# cm_filter_ch1_a.net
KiCad netlist of a schematic drawn in Altium Designer
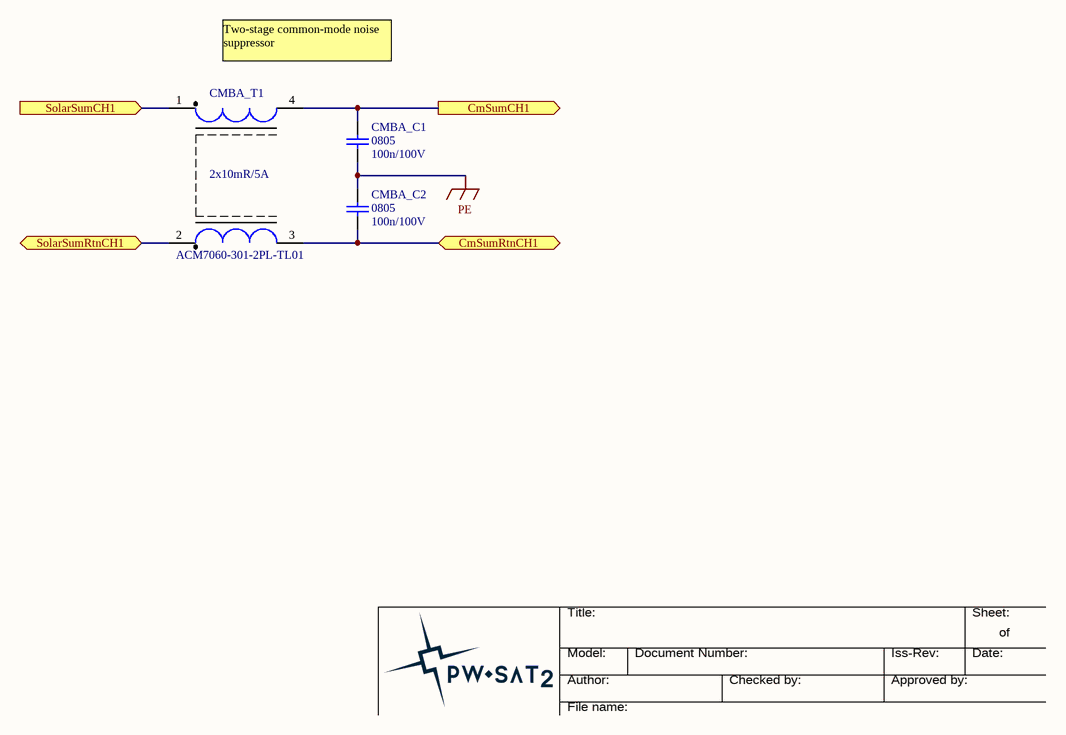
[diagram p0: cm_filter_ch1_a.SchDoc]

(export (version "E")
  (design (tool "Eeschema 10.0.6"))
  (components
    (comp (ref "CMBA_C1")
      (value "100n/100V")
      (footprint "SMD_Capacitor_0805")
      (description "Ceramic Cap Kemet COTS 100n/100V X7R 0805")
      (fields
        (field (name "MANUFACTURERPARTNUMBER") "C0805T104K1RCLTU")
        (field (name "MANUFACTURER") "Kemet")
        (field (name "PACKAGE") "0805")
      )
      (libsource (lib "capacitors") (part "Cer_C0805T104K1RCLTU"))
    )
    (comp (ref "CMBA_C2")
      (value "100n/100V")
      (footprint "SMD_Capacitor_0805")
      (description "Ceramic Cap Kemet COTS 100n/100V X7R 0805")
      (fields
        (field (name "MANUFACTURERPARTNUMBER") "C0805T104K1RCLTU")
        (field (name "MANUFACTURER") "Kemet")
        (field (name "PACKAGE") "0805")
      )
      (libsource (lib "capacitors") (part "Cer_C0805T104K1RCLTU"))
    )
    (comp (ref "CMBA_T1")
      (value "2x10mR/5A")
      (footprint "TDK_ACM7060")
      (description "TDK ACM7060-301 Common Mode Choke")
      (fields
        (field (name "MANUFACTURER") "TDK")
        (field (name "MANUFACTURERPARTNUMBER") "ACM7060-301-2PL-TL01")
      )
      (libsource (lib "inductors_cores") (part "ACM7060-301-2PL-TL01"))
    )
  )
  (nets
    (net (code "1") (name "/CmSumCH1") (class "Default")
      (node (ref "CMBA_C1") (pin "1") (pinfunction "1_1") (pintype "passive"))
      (node (ref "CMBA_T1") (pin "4") (pinfunction "4_4") (pintype "passive"))
    )
    (net (code "2") (name "/CmSumRtnCH1") (class "Default")
      (node (ref "CMBA_C2") (pin "2") (pinfunction "2_2") (pintype "passive"))
      (node (ref "CMBA_T1") (pin "3") (pinfunction "3_3") (pintype "passive"))
    )
    (net (code "3") (name "/SolarSumCH1") (class "Default")
      (node (ref "CMBA_T1") (pin "1") (pinfunction "1_1") (pintype "passive"))
    )
    (net (code "4") (name "/SolarSumRtnCH1") (class "Default")
      (node (ref "CMBA_T1") (pin "2") (pinfunction "2_2") (pintype "passive"))
    )
    (net (code "5") (name "PE") (class "Default")
      (node (ref "CMBA_C1") (pin "2") (pinfunction "2_2") (pintype "passive"))
      (node (ref "CMBA_C2") (pin "1") (pinfunction "1_1") (pintype "passive"))
    )
  )
)
